# 2242_project_part_brd.net
KiCad netlist of a schematic drawn in EAGLE
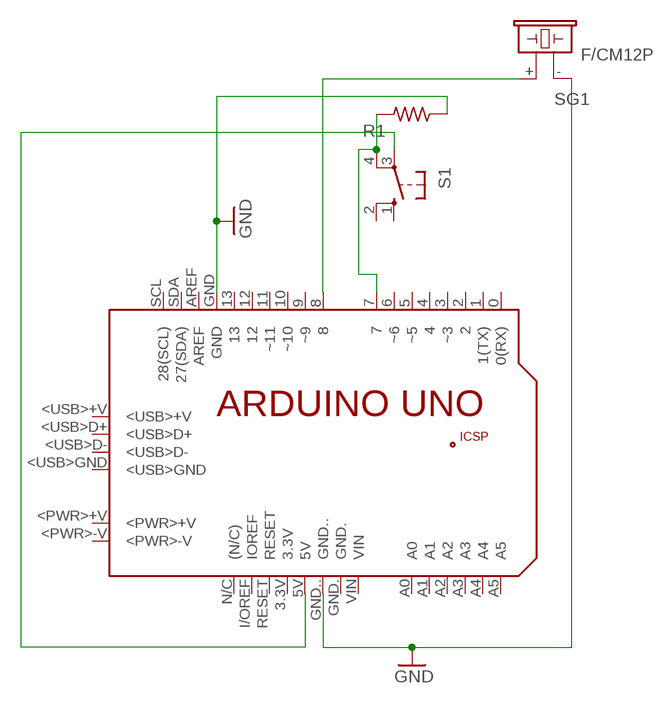
[diagram p0: schematic, sheet 1]

(export (version "E")
  (design (tool "Eeschema 10.0.6"))
  (components
    (comp (ref "PCB1")
      (value "ARDUINO_UNO")
      (footprint "eagle-import:ARDUINO_UNO")
      (libsource (lib "eagle-import") (part "ARDUINO_UNO"))
    )
    (comp (ref "R1")
      (value "R-US_0204/2V")
      (footprint "eagle-import:0204V")
      (libsource (lib "eagle-import") (part "R-US_0204/2V"))
    )
    (comp (ref "S1")
      (value "10-XX")
      (footprint "eagle-import:B3F-10XX")
      (fields (field (name "MPN") "B3F-1000"))
      (libsource (lib "eagle-import") (part "10-XX"))
    )
    (comp (ref "SG1")
      (value "F/CM12P")
      (footprint "eagle-import:F_CM12P")
      (libsource (lib "eagle-import") (part "F/CM12P"))
    )
  )
  (nets
    (net (code "1") (name "GND") (class "Default")
      (node (ref "PCB1") (pin "GND") (pinfunction "GND_GND") (pintype "bidirectional"))
      (node (ref "PCB1") (pin "GND..") (pinfunction "GND.._GND..") (pintype "bidirectional"))
      (node (ref "R1") (pin "1") (pinfunction "1_1") (pintype "passive"))
      (node (ref "SG1") (pin "-") (pinfunction "2_-") (pintype "passive"))
    )
    (net (code "2") (name "Net-(S1-P)") (class "Default")
      (node (ref "PCB1") (pin "5V") (pinfunction "5V_5V") (pintype "bidirectional"))
      (node (ref "S1") (pin "3") (pinfunction "P_3") (pintype "passive"))
    )
    (net (code "3") (name "Net-(S1-P1)") (class "Default")
      (node (ref "PCB1") (pin "7") (pinfunction "7_7") (pintype "bidirectional"))
      (node (ref "R1") (pin "2") (pinfunction "2_2") (pintype "passive"))
      (node (ref "S1") (pin "4") (pinfunction "P1_4") (pintype "passive"))
    )
    (net (code "4") (name "Net-(SG1-1)") (class "Default")
      (node (ref "PCB1") (pin "8") (pinfunction "8_8") (pintype "bidirectional"))
      (node (ref "SG1") (pin "+") (pinfunction "1_+") (pintype "passive"))
    )
    (net (code "5") (name "unconnected-(PCB1-(N{slash}C)-PadN{slash}C)") (class "Default")
      (node (ref "PCB1") (pin "N/C") (pinfunction "(N/C)_N/C") (pintype "bidirectional"))
    )
    (net (code "6") (name "unconnected-(PCB1-0(RX)-Pad0)") (class "Default")
      (node (ref "PCB1") (pin "0") (pinfunction "0(RX)_0") (pintype "bidirectional"))
    )
    (net (code "7") (name "unconnected-(PCB1-1(TX)-Pad1)") (class "Default")
      (node (ref "PCB1") (pin "1") (pinfunction "1(TX)_1") (pintype "bidirectional"))
    )
    (net (code "8") (name "unconnected-(PCB1-27(SDA)-PadSDA)") (class "Default")
      (node (ref "PCB1") (pin "SDA") (pinfunction "27(SDA)_SDA") (pintype "bidirectional"))
    )
    (net (code "9") (name "unconnected-(PCB1-28(SCL)-PadSCL)") (class "Default")
      (node (ref "PCB1") (pin "SCL") (pinfunction "28(SCL)_SCL") (pintype "bidirectional"))
    )
    (net (code "10") (name "unconnected-(PCB1-IOREF-PadI{slash}OREF)") (class "Default")
      (node (ref "PCB1") (pin "I/OREF") (pinfunction "IOREF_I/OREF") (pintype "bidirectional"))
    )
    (net (code "11") (name "unconnected-(PCB1-Pad+5V)") (class "Default")
      (node (ref "PCB1") (pin "+5V") (pinfunction "+5V_+5V") (pintype "bidirectional"))
    )
    (net (code "12") (name "unconnected-(PCB1-Pad2)") (class "Default")
      (node (ref "PCB1") (pin "2") (pinfunction "2_2") (pintype "bidirectional"))
    )
    (net (code "13") (name "unconnected-(PCB1-Pad3.3V)") (class "Default")
      (node (ref "PCB1") (pin "3.3V") (pinfunction "3.3V_3.3V") (pintype "bidirectional"))
    )
    (net (code "14") (name "unconnected-(PCB1-Pad4)") (class "Default")
      (node (ref "PCB1") (pin "4") (pinfunction "4_4") (pintype "bidirectional"))
    )
    (net (code "15") (name "unconnected-(PCB1-Pad12)") (class "Default")
      (node (ref "PCB1") (pin "12") (pinfunction "12_12") (pintype "bidirectional"))
    )
    (net (code "16") (name "unconnected-(PCB1-Pad13)") (class "Default")
      (node (ref "PCB1") (pin "13") (pinfunction "13_13") (pintype "bidirectional"))
    )
    (net (code "17") (name "unconnected-(PCB1-Pad<PWR>+V)") (class "Default")
      (node (ref "PCB1") (pin "<PWR>+V") (pinfunction "<PWR>+V_<PWR>+V") (pintype "bidirectional"))
    )
    (net (code "18") (name "unconnected-(PCB1-Pad<PWR>-V)") (class "Default")
      (node (ref "PCB1") (pin "<PWR>-V") (pinfunction "<PWR>-V_<PWR>-V") (pintype "bidirectional"))
    )
    (net (code "19") (name "unconnected-(PCB1-Pad<USB>+V)") (class "Default")
      (node (ref "PCB1") (pin "<USB>+V") (pinfunction "<USB>+V_<USB>+V") (pintype "bidirectional"))
    )
    (net (code "20") (name "unconnected-(PCB1-Pad<USB>D+)") (class "Default")
      (node (ref "PCB1") (pin "<USB>D+") (pinfunction "<USB>D+_<USB>D+") (pintype "bidirectional"))
    )
    (net (code "21") (name "unconnected-(PCB1-Pad<USB>D-)") (class "Default")
      (node (ref "PCB1") (pin "<USB>D-") (pinfunction "<USB>D-_<USB>D-") (pintype "bidirectional"))
    )
    (net (code "22") (name "unconnected-(PCB1-Pad<USB>GND)") (class "Default")
      (node (ref "PCB1") (pin "<USB>GND") (pinfunction "<USB>GND_<USB>GND") (pintype "bidirectional"))
    )
    (net (code "23") (name "unconnected-(PCB1-PadA0)") (class "Default")
      (node (ref "PCB1") (pin "A0") (pinfunction "A0_A0") (pintype "bidirectional"))
    )
    (net (code "24") (name "unconnected-(PCB1-PadA1)") (class "Default")
      (node (ref "PCB1") (pin "A1") (pinfunction "A1_A1") (pintype "bidirectional"))
    )
    (net (code "25") (name "unconnected-(PCB1-PadA2)") (class "Default")
      (node (ref "PCB1") (pin "A2") (pinfunction "A2_A2") (pintype "bidirectional"))
    )
    (net (code "26") (name "unconnected-(PCB1-PadA3)") (class "Default")
      (node (ref "PCB1") (pin "A3") (pinfunction "A3_A3") (pintype "bidirectional"))
    )
    (net (code "27") (name "unconnected-(PCB1-PadA4)") (class "Default")
      (node (ref "PCB1") (pin "A4") (pinfunction "A4_A4") (pintype "bidirectional"))
    )
    (net (code "28") (name "unconnected-(PCB1-PadA5)") (class "Default")
      (node (ref "PCB1") (pin "A5") (pinfunction "A5_A5") (pintype "bidirectional"))
    )
    (net (code "29") (name "unconnected-(PCB1-PadAREF)") (class "Default")
      (node (ref "PCB1") (pin "AREF") (pinfunction "AREF_AREF") (pintype "bidirectional"))
    )
    (net (code "30") (name "unconnected-(PCB1-PadGND.)") (class "Default")
      (node (ref "PCB1") (pin "GND.") (pinfunction "GND._GND.") (pintype "bidirectional"))
    )
    (net (code "31") (name "unconnected-(PCB1-PadGND_)") (class "Default")
      (node (ref "PCB1") (pin "GND_") (pinfunction "GND__GND_") (pintype "bidirectional"))
    )
    (net (code "32") (name "unconnected-(PCB1-PadMISO)") (class "Default")
      (node (ref "PCB1") (pin "MISO") (pinfunction "MISO_MISO") (pintype "bidirectional"))
    )
    (net (code "33") (name "unconnected-(PCB1-PadMOSI)") (class "Default")
      (node (ref "PCB1") (pin "MOSI") (pinfunction "MOSI_MOSI") (pintype "bidirectional"))
    )
    (net (code "34") (name "unconnected-(PCB1-PadRESET)") (class "Default")
      (node (ref "PCB1") (pin "RESET") (pinfunction "RESET_RESET") (pintype "bidirectional"))
    )
    (net (code "35") (name "unconnected-(PCB1-PadRESET.)") (class "Default")
      (node (ref "PCB1") (pin "RESET.") (pinfunction "RESET._RESET.") (pintype "bidirectional"))
    )
    (net (code "36") (name "unconnected-(PCB1-PadSCK)") (class "Default")
      (node (ref "PCB1") (pin "SCK") (pinfunction "SCK_SCK") (pintype "bidirectional"))
    )
    (net (code "37") (name "unconnected-(PCB1-PadVIN)") (class "Default")
      (node (ref "PCB1") (pin "VIN") (pinfunction "VIN_VIN") (pintype "bidirectional"))
    )
    (net (code "38") (name "unconnected-(PCB1-~{3}-Pad3)") (class "Default")
      (node (ref "PCB1") (pin "3") (pinfunction "~{3}_3") (pintype "bidirectional"))
    )
    (net (code "39") (name "unconnected-(PCB1-~{5}-Pad5)") (class "Default")
      (node (ref "PCB1") (pin "5") (pinfunction "~{5}_5") (pintype "bidirectional"))
    )
    (net (code "40") (name "unconnected-(PCB1-~{6}-Pad6)") (class "Default")
      (node (ref "PCB1") (pin "6") (pinfunction "~{6}_6") (pintype "bidirectional"))
    )
    (net (code "41") (name "unconnected-(PCB1-~{9}-Pad9)") (class "Default")
      (node (ref "PCB1") (pin "9") (pinfunction "~{9}_9") (pintype "bidirectional"))
    )
    (net (code "42") (name "unconnected-(PCB1-~{10}-Pad10)") (class "Default")
      (node (ref "PCB1") (pin "10") (pinfunction "~{10}_10") (pintype "bidirectional"))
    )
    (net (code "43") (name "unconnected-(PCB1-~{11}-Pad11)") (class "Default")
      (node (ref "PCB1") (pin "11") (pinfunction "~{11}_11") (pintype "bidirectional"))
    )
    (net (code "44") (name "unconnected-(S1-S-Pad1)") (class "Default")
      (node (ref "S1") (pin "1") (pinfunction "S_1") (pintype "passive"))
    )
    (net (code "45") (name "unconnected-(S1-S1-Pad2)") (class "Default")
      (node (ref "S1") (pin "2") (pinfunction "S1_2") (pintype "passive"))
    )
  )
)
